# POWER.net
KiCad netlist of a schematic drawn in Altium Designer
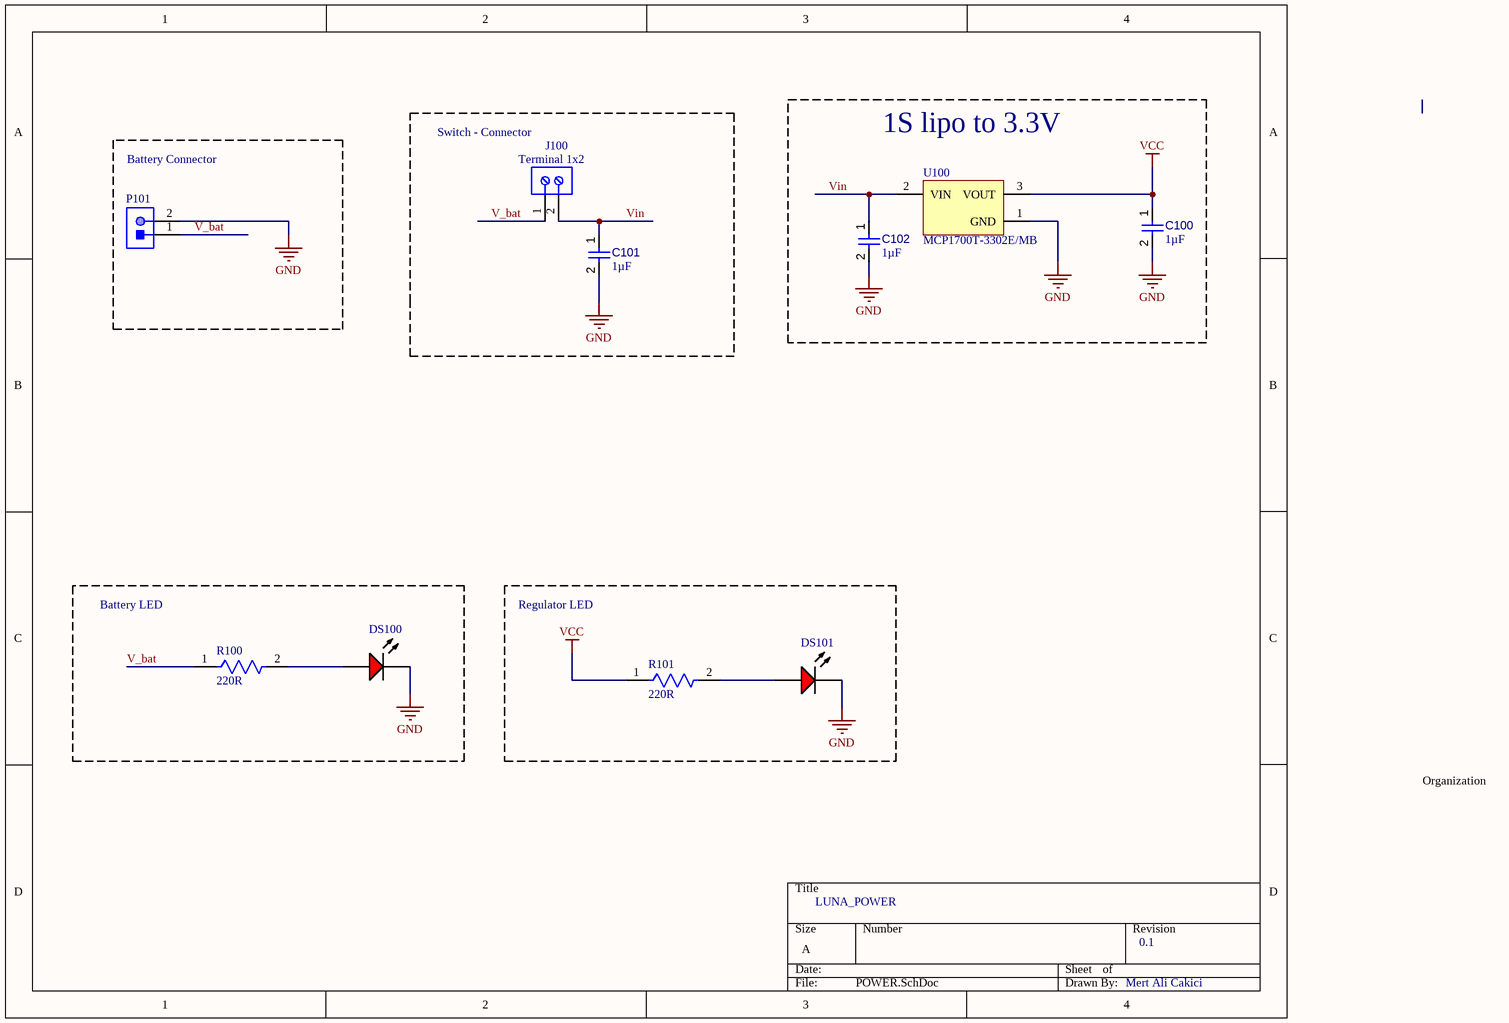
[diagram p0: POWER.SchDoc]

(export (version "E")
  (design (tool "Eeschema 10.0.6"))
  (components
    (comp (ref "C100")
      (value "1µF")
      (footprint "CAPC1608X90X35NL15T15")
      (description "Chip Capacitor, 1 uF, +/- 10%, 16 V, 0603 (1608 Metric)")
      (fields (field (name "TOLERANCE") "10%") (field (name "Comment") "Capacitor 1uF +/- 10% 16V 0603"))
      (libsource (lib "Mert ALi Çakıcı") (part "CAP-NP-2"))
    )
    (comp (ref "C101")
      (value "1µF")
      (footprint "CAPC1608X90X35NL15T15")
      (description "Chip Capacitor, 1 uF, +/- 10%, 16 V, 0603 (1608 Metric)")
      (fields (field (name "TOLERANCE") "10%") (field (name "Comment") "Capacitor 1uF +/- 10% 16V 0603"))
      (libsource (lib "Mert ALi Çakıcı") (part "CAP-NP-2"))
    )
    (comp (ref "C102")
      (value "1µF")
      (footprint "CAPC1608X90X35NL15T15")
      (description "Chip Capacitor, 1 uF, +/- 10%, 16 V, 0603 (1608 Metric)")
      (fields (field (name "TOLERANCE") "10%") (field (name "Comment") "Capacitor 1uF +/- 10% 16V 0603"))
      (libsource (lib "Mert ALi Çakıcı") (part "CAP-NP-2"))
    )
    (comp (ref "DS100")
      (value "19-217/R6C-AL1M2VY/3T")
      (footprint "EVRL-0603-2_V")
      (description "Chip LED, Red, 5 V, 25 mA, -40 to 85 degC, 2-Pin SMD (0603), RoHS, Tape and Reel")
      (fields (field (name "MANUFACTURER") "Everlight Electronics"))
      (libsource (lib "Mert ALi Çakıcı") (part "LED-RED-AK-2"))
    )
    (comp (ref "DS101")
      (value "19-217/R6C-AL1M2VY/3T")
      (footprint "EVRL-0603-2_V")
      (description "Chip LED, Red, 5 V, 25 mA, -40 to 85 degC, 2-Pin SMD (0603), RoHS, Tape and Reel")
      (fields (field (name "MANUFACTURER") "Everlight Electronics"))
      (libsource (lib "Mert ALi Çakıcı") (part "LED-RED-AK-2"))
    )
    (comp (ref "J100")
      (value "Terminal 1x2")
      (footprint "TECO-282836-2_V")
      (description "Female Header, Pitch 5 mm, 1 x 2 Position, Height 10 mm, Tail Length 3.5 mm, Rohs, Bulk")
      (fields (field (name "VOLTAGE") "300V") (field (name "MANUFACTURER") "TE Connectivity"))
      (libsource (lib "Altium Content Vault") (part "CN-1P-F-TB2"))
    )
    (comp (ref "P101")
      (value "S2B-XH-A(LF)(SN)")
      (footprint "JST-S2B-XH-A(LF)(SN)_V")
      (fields (field (name "MANUFACTURER") "JST"))
      (libsource (lib "Mert ALi Çakıcı") (part "CN-1P-M-R2"))
    )
    (comp (ref "R100")
      (value "220R")
      (footprint "FP-CRCW0603-e3-MFG")
      (description "RES Thick Film, 220Ω, 1%, 0.1W, 100ppm/°C, 0603")
      (fields (field (name "TOLERANCE") "1%"))
      (libsource (lib "Altium Content Vault") (part "1029c3af85768c4190bb7ad29bc67b5"))
    )
    (comp (ref "R101")
      (value "220R")
      (footprint "FP-CRCW0603-e3-MFG")
      (description "RES Thick Film, 220Ω, 1%, 0.1W, 100ppm/°C, 0603")
      (fields (field (name "TOLERANCE") "1%"))
      (libsource (lib "Altium Content Vault") (part "1029c3af85768c4190bb7ad29bc67b5"))
    )
    (comp (ref "U100")
      (value "MCP1700T-3302E/MB")
      (footprint "SOT-89-MB3_M")
      (description "Low Quiescent Current LDO, 3-Pin SOT-89, Extended Temperature, Tape and Reel")
      (libsource (lib "Altium Content Vault") (part "PM-LINEREG-MCP1700-IL3A"))
    )
  )
  (nets
    (net (code "1") (name "/V_bat") (class "Default")
      (node (ref "J100") (pin "1") (pinfunction "1_1") (pintype "passive"))
      (node (ref "P101") (pin "1") (pinfunction "1_1") (pintype "passive"))
      (node (ref "R100") (pin "1") (pinfunction "1_1") (pintype "passive"))
    )
    (net (code "2") (name "/Vin") (class "Default")
      (node (ref "C101") (pin "1") (pinfunction "1_1") (pintype "passive"))
      (node (ref "C102") (pin "1") (pinfunction "1_1") (pintype "passive"))
      (node (ref "J100") (pin "2") (pinfunction "2_2") (pintype "passive"))
      (node (ref "U100") (pin "2") (pinfunction "VIN_2") (pintype "power_in"))
    )
    (net (code "3") (name "GND") (class "Default")
      (node (ref "C100") (pin "2") (pinfunction "2_2") (pintype "passive"))
      (node (ref "C101") (pin "2") (pinfunction "2_2") (pintype "passive"))
      (node (ref "C102") (pin "2") (pinfunction "2_2") (pintype "passive"))
      (node (ref "DS100") (pin "2") (pinfunction "K_2") (pintype "passive"))
      (node (ref "DS101") (pin "2") (pinfunction "K_2") (pintype "passive"))
      (node (ref "P101") (pin "2") (pinfunction "2_2") (pintype "passive"))
      (node (ref "U100") (pin "1") (pinfunction "GND_1") (pintype "power_in"))
    )
    (net (code "4") (name "Net-(DS100-A)") (class "Default")
      (node (ref "DS100") (pin "1") (pinfunction "A_1") (pintype "passive"))
      (node (ref "R100") (pin "2") (pinfunction "2_2") (pintype "passive"))
    )
    (net (code "5") (name "Net-(DS101-A)") (class "Default")
      (node (ref "DS101") (pin "1") (pinfunction "A_1") (pintype "passive"))
      (node (ref "R101") (pin "2") (pinfunction "2_2") (pintype "passive"))
    )
    (net (code "6") (name "VCC") (class "Default")
      (node (ref "C100") (pin "1") (pinfunction "1_1") (pintype "passive"))
      (node (ref "R101") (pin "1") (pinfunction "1_1") (pintype "passive"))
      (node (ref "U100") (pin "3") (pinfunction "VOUT_3") (pintype "power_in"))
    )
  )
)
